# 2_matrix.net
KiCad netlist of a schematic drawn in Altium Designer
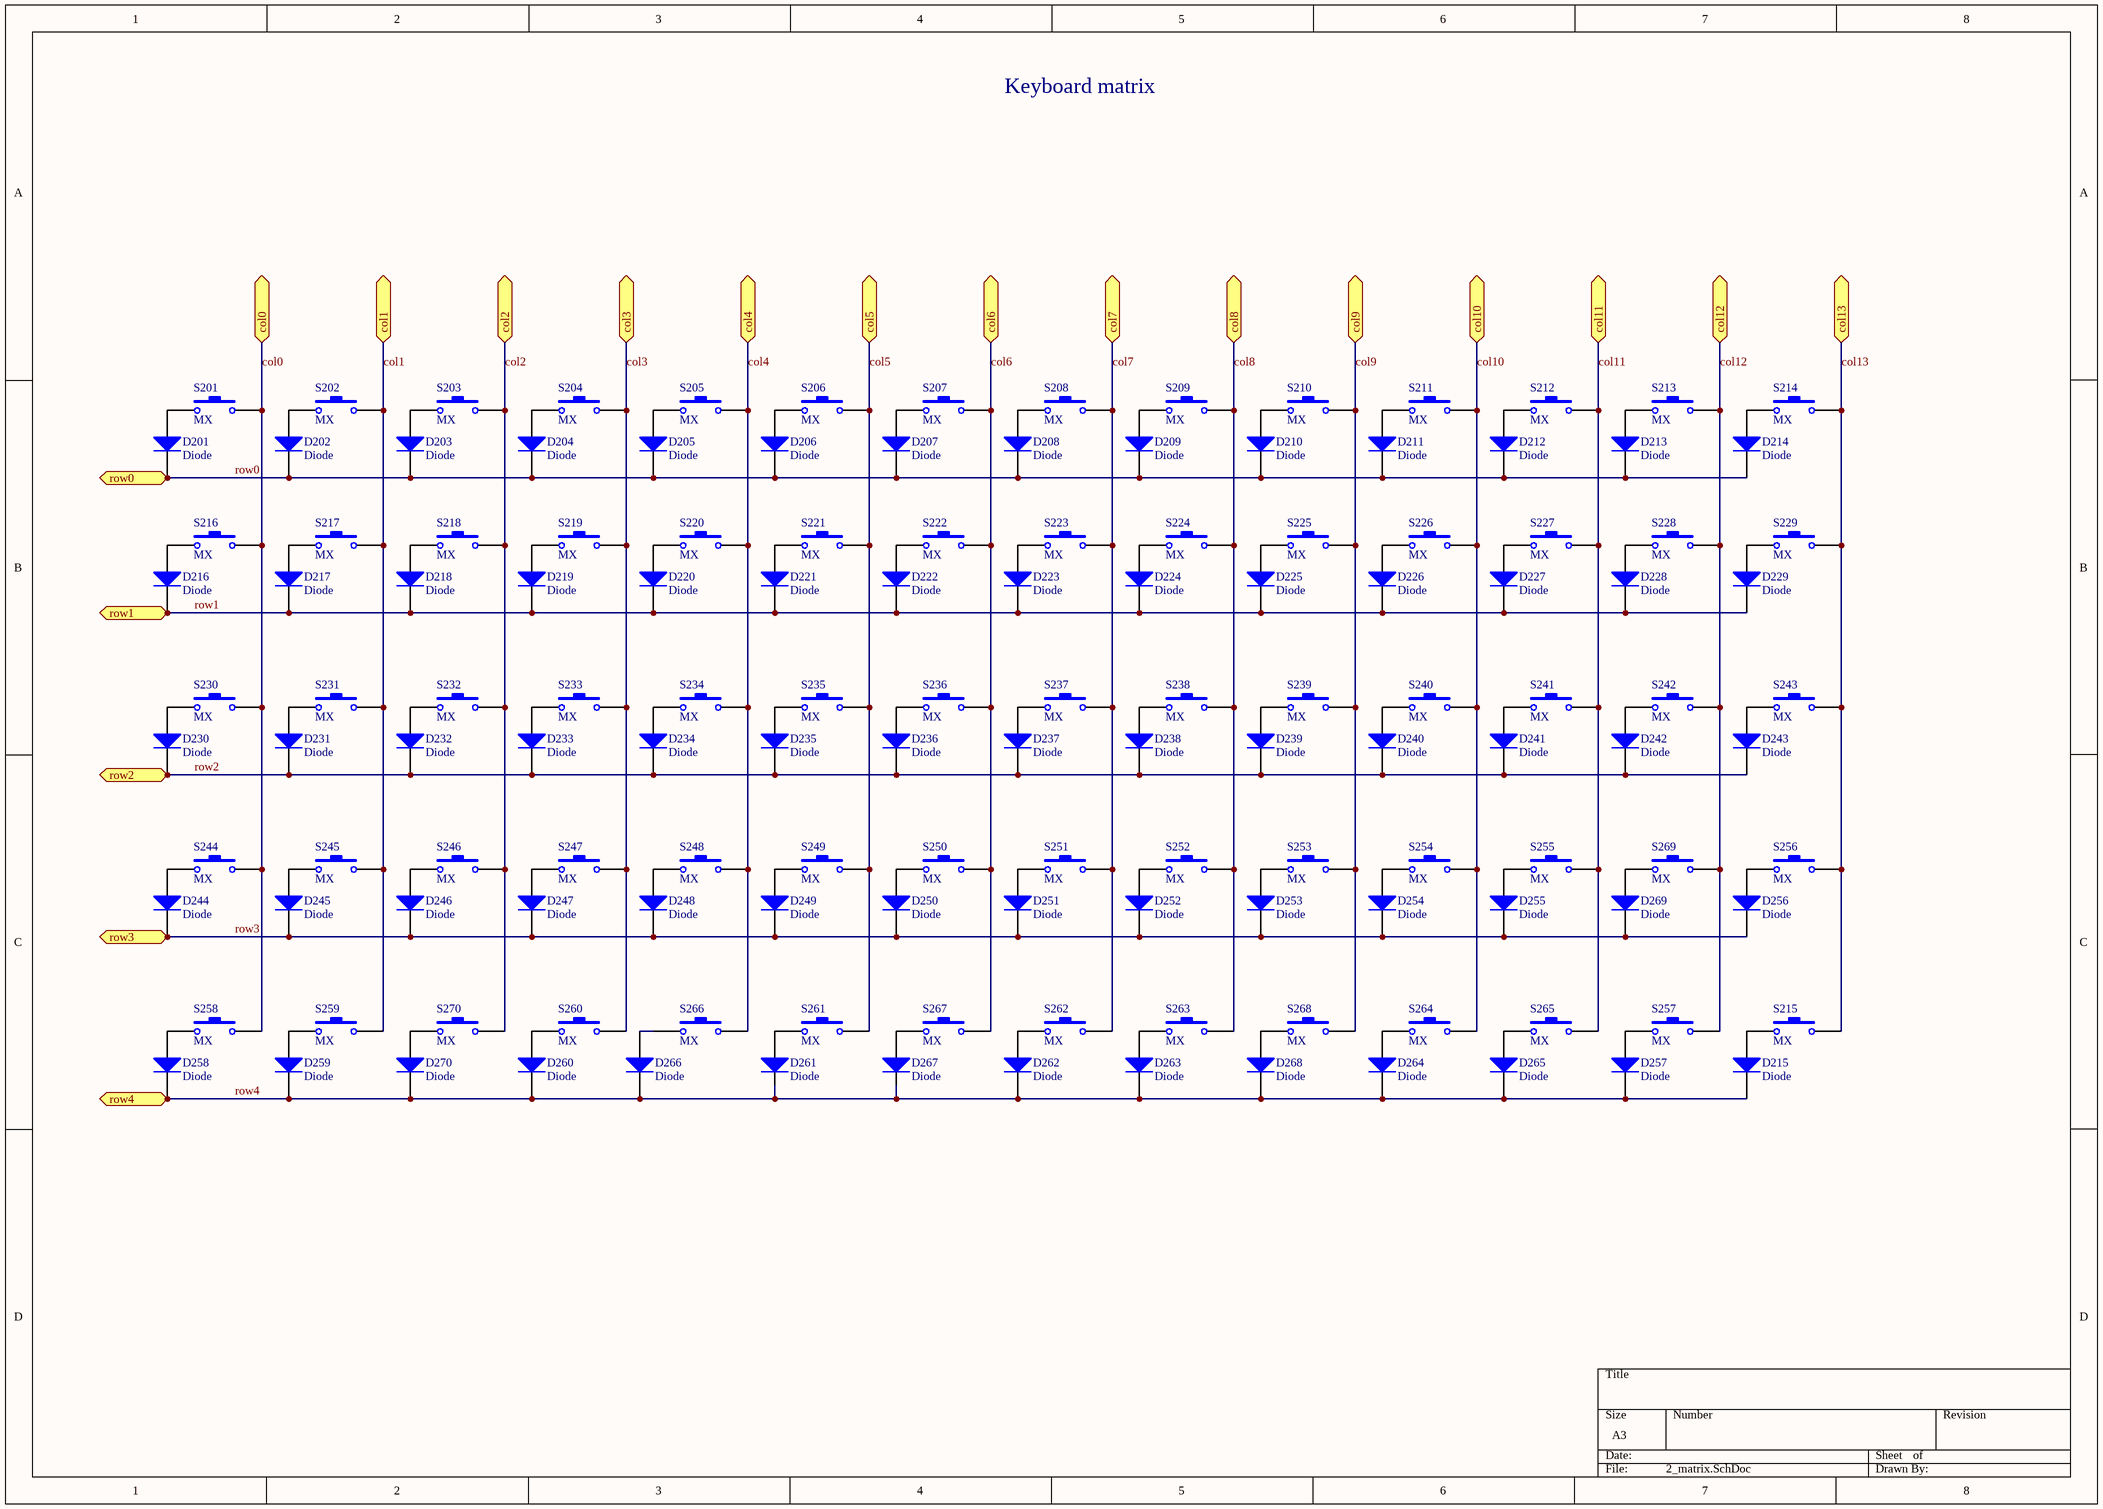
[diagram p0: 2_matrix.SchDoc]

(export (version "E")
  (design (tool "Eeschema 10.0.6"))
  (components
    (comp (ref "D201")
      (value "Diode")
      (footprint "D0603[1608]")
      (description "Default Diode")
      (fields (field (name "MFG") "Bourns Inc.") (field (name "MRF.PART") "CD4148WTP"))
      (libsource (lib "Miscellaneous Devices") (part "Diode"))
    )
    (comp (ref "D202")
      (value "Diode")
      (footprint "D0603[1608]")
      (description "Default Diode")
      (fields (field (name "MFG") "Bourns Inc.") (field (name "MRF.PART") "CD4148WTP"))
      (libsource (lib "Miscellaneous Devices") (part "Diode"))
    )
    (comp (ref "D203")
      (value "Diode")
      (footprint "D0603[1608]")
      (description "Default Diode")
      (fields (field (name "MFG") "Bourns Inc.") (field (name "MRF.PART") "CD4148WTP"))
      (libsource (lib "Miscellaneous Devices") (part "Diode"))
    )
    (comp (ref "D204")
      (value "Diode")
      (footprint "D0603[1608]")
      (description "Default Diode")
      (fields (field (name "MFG") "Bourns Inc.") (field (name "MRF.PART") "CD4148WTP"))
      (libsource (lib "Miscellaneous Devices") (part "Diode"))
    )
    (comp (ref "D205")
      (value "Diode")
      (footprint "D0603[1608]")
      (description "Default Diode")
      (fields (field (name "MFG") "Bourns Inc.") (field (name "MRF.PART") "CD4148WTP"))
      (libsource (lib "Miscellaneous Devices") (part "Diode"))
    )
    (comp (ref "D206")
      (value "Diode")
      (footprint "D0603[1608]")
      (description "Default Diode")
      (fields (field (name "MFG") "Bourns Inc.") (field (name "MRF.PART") "CD4148WTP"))
      (libsource (lib "Miscellaneous Devices") (part "Diode"))
    )
    (comp (ref "D207")
      (value "Diode")
      (footprint "D0603[1608]")
      (description "Default Diode")
      (fields (field (name "MFG") "Bourns Inc.") (field (name "MRF.PART") "CD4148WTP"))
      (libsource (lib "Miscellaneous Devices") (part "Diode"))
    )
    (comp (ref "D208")
      (value "Diode")
      (footprint "D0603[1608]")
      (description "Default Diode")
      (fields (field (name "MFG") "Bourns Inc.") (field (name "MRF.PART") "CD4148WTP"))
      (libsource (lib "Miscellaneous Devices") (part "Diode"))
    )
    (comp (ref "D209")
      (value "Diode")
      (footprint "D0603[1608]")
      (description "Default Diode")
      (fields (field (name "MFG") "Bourns Inc.") (field (name "MRF.PART") "CD4148WTP"))
      (libsource (lib "Miscellaneous Devices") (part "Diode"))
    )
    (comp (ref "D210")
      (value "Diode")
      (footprint "D0603[1608]")
      (description "Default Diode")
      (fields (field (name "MFG") "Bourns Inc.") (field (name "MRF.PART") "CD4148WTP"))
      (libsource (lib "Miscellaneous Devices") (part "Diode"))
    )
    (comp (ref "D211")
      (value "Diode")
      (footprint "D0603[1608]")
      (description "Default Diode")
      (fields (field (name "MFG") "Bourns Inc.") (field (name "MRF.PART") "CD4148WTP"))
      (libsource (lib "Miscellaneous Devices") (part "Diode"))
    )
    (comp (ref "D212")
      (value "Diode")
      (footprint "D0603[1608]")
      (description "Default Diode")
      (fields (field (name "MFG") "Bourns Inc.") (field (name "MRF.PART") "CD4148WTP"))
      (libsource (lib "Miscellaneous Devices") (part "Diode"))
    )
    (comp (ref "D213")
      (value "Diode")
      (footprint "D0603[1608]")
      (description "Default Diode")
      (fields (field (name "MFG") "Bourns Inc.") (field (name "MRF.PART") "CD4148WTP"))
      (libsource (lib "Miscellaneous Devices") (part "Diode"))
    )
    (comp (ref "D214")
      (value "Diode")
      (footprint "D0603[1608]")
      (description "Default Diode")
      (fields (field (name "MFG") "Bourns Inc.") (field (name "MRF.PART") "CD4148WTP"))
      (libsource (lib "Miscellaneous Devices") (part "Diode"))
    )
    (comp (ref "D215")
      (value "Diode")
      (footprint "D0603[1608]")
      (description "Default Diode")
      (fields (field (name "MFG") "Bourns Inc.") (field (name "MRF.PART") "CD4148WTP"))
      (libsource (lib "Miscellaneous Devices") (part "Diode"))
    )
    (comp (ref "D216")
      (value "Diode")
      (footprint "D0603[1608]")
      (description "Default Diode")
      (fields (field (name "MFG") "Bourns Inc.") (field (name "MRF.PART") "CD4148WTP"))
      (libsource (lib "Miscellaneous Devices") (part "Diode"))
    )
    (comp (ref "D217")
      (value "Diode")
      (footprint "D0603[1608]")
      (description "Default Diode")
      (fields (field (name "MFG") "Bourns Inc.") (field (name "MRF.PART") "CD4148WTP"))
      (libsource (lib "Miscellaneous Devices") (part "Diode"))
    )
    (comp (ref "D218")
      (value "Diode")
      (footprint "D0603[1608]")
      (description "Default Diode")
      (fields (field (name "MFG") "Bourns Inc.") (field (name "MRF.PART") "CD4148WTP"))
      (libsource (lib "Miscellaneous Devices") (part "Diode"))
    )
    (comp (ref "D219")
      (value "Diode")
      (footprint "D0603[1608]")
      (description "Default Diode")
      (fields (field (name "MFG") "Bourns Inc.") (field (name "MRF.PART") "CD4148WTP"))
      (libsource (lib "Miscellaneous Devices") (part "Diode"))
    )
    (comp (ref "D220")
      (value "Diode")
      (footprint "D0603[1608]")
      (description "Default Diode")
      (fields (field (name "MFG") "Bourns Inc.") (field (name "MRF.PART") "CD4148WTP"))
      (libsource (lib "Miscellaneous Devices") (part "Diode"))
    )
    (comp (ref "D221")
      (value "Diode")
      (footprint "D0603[1608]")
      (description "Default Diode")
      (fields (field (name "MFG") "Bourns Inc.") (field (name "MRF.PART") "CD4148WTP"))
      (libsource (lib "Miscellaneous Devices") (part "Diode"))
    )
    (comp (ref "D222")
      (value "Diode")
      (footprint "D0603[1608]")
      (description "Default Diode")
      (fields (field (name "MFG") "Bourns Inc.") (field (name "MRF.PART") "CD4148WTP"))
      (libsource (lib "Miscellaneous Devices") (part "Diode"))
    )
    (comp (ref "D223")
      (value "Diode")
      (footprint "D0603[1608]")
      (description "Default Diode")
      (fields (field (name "MFG") "Bourns Inc.") (field (name "MRF.PART") "CD4148WTP"))
      (libsource (lib "Miscellaneous Devices") (part "Diode"))
    )
    (comp (ref "D224")
      (value "Diode")
      (footprint "D0603[1608]")
      (description "Default Diode")
      (fields (field (name "MFG") "Bourns Inc.") (field (name "MRF.PART") "CD4148WTP"))
      (libsource (lib "Miscellaneous Devices") (part "Diode"))
    )
    (comp (ref "D225")
      (value "Diode")
      (footprint "D0603[1608]")
      (description "Default Diode")
      (fields (field (name "MFG") "Bourns Inc.") (field (name "MRF.PART") "CD4148WTP"))
      (libsource (lib "Miscellaneous Devices") (part "Diode"))
    )
    (comp (ref "D226")
      (value "Diode")
      (footprint "D0603[1608]")
      (description "Default Diode")
      (fields (field (name "MFG") "Bourns Inc.") (field (name "MRF.PART") "CD4148WTP"))
      (libsource (lib "Miscellaneous Devices") (part "Diode"))
    )
    (comp (ref "D227")
      (value "Diode")
      (footprint "D0603[1608]")
      (description "Default Diode")
      (fields (field (name "MFG") "Bourns Inc.") (field (name "MRF.PART") "CD4148WTP"))
      (libsource (lib "Miscellaneous Devices") (part "Diode"))
    )
    (comp (ref "D228")
      (value "Diode")
      (footprint "D0603[1608]")
      (description "Default Diode")
      (fields (field (name "MFG") "Bourns Inc.") (field (name "MRF.PART") "CD4148WTP"))
      (libsource (lib "Miscellaneous Devices") (part "Diode"))
    )
    (comp (ref "D229")
      (value "Diode")
      (footprint "D0603[1608]")
      (description "Default Diode")
      (fields (field (name "MFG") "Bourns Inc.") (field (name "MRF.PART") "CD4148WTP"))
      (libsource (lib "Miscellaneous Devices") (part "Diode"))
    )
    (comp (ref "D230")
      (value "Diode")
      (footprint "D0603[1608]")
      (description "Default Diode")
      (fields (field (name "MFG") "Bourns Inc.") (field (name "MRF.PART") "CD4148WTP"))
      (libsource (lib "Miscellaneous Devices") (part "Diode"))
    )
    (comp (ref "D231")
      (value "Diode")
      (footprint "D0603[1608]")
      (description "Default Diode")
      (fields (field (name "MFG") "Bourns Inc.") (field (name "MRF.PART") "CD4148WTP"))
      (libsource (lib "Miscellaneous Devices") (part "Diode"))
    )
    (comp (ref "D232")
      (value "Diode")
      (footprint "D0603[1608]")
      (description "Default Diode")
      (fields (field (name "MFG") "Bourns Inc.") (field (name "MRF.PART") "CD4148WTP"))
      (libsource (lib "Miscellaneous Devices") (part "Diode"))
    )
    (comp (ref "D233")
      (value "Diode")
      (footprint "D0603[1608]")
      (description "Default Diode")
      (fields (field (name "MFG") "Bourns Inc.") (field (name "MRF.PART") "CD4148WTP"))
      (libsource (lib "Miscellaneous Devices") (part "Diode"))
    )
    (comp (ref "D234")
      (value "Diode")
      (footprint "D0603[1608]")
      (description "Default Diode")
      (fields (field (name "MFG") "Bourns Inc.") (field (name "MRF.PART") "CD4148WTP"))
      (libsource (lib "Miscellaneous Devices") (part "Diode"))
    )
    (comp (ref "D235")
      (value "Diode")
      (footprint "D0603[1608]")
      (description "Default Diode")
      (fields (field (name "MFG") "Bourns Inc.") (field (name "MRF.PART") "CD4148WTP"))
      (libsource (lib "Miscellaneous Devices") (part "Diode"))
    )
    (comp (ref "D236")
      (value "Diode")
      (footprint "D0603[1608]")
      (description "Default Diode")
      (fields (field (name "MFG") "Bourns Inc.") (field (name "MRF.PART") "CD4148WTP"))
      (libsource (lib "Miscellaneous Devices") (part "Diode"))
    )
    (comp (ref "D237")
      (value "Diode")
      (footprint "D0603[1608]")
      (description "Default Diode")
      (fields (field (name "MFG") "Bourns Inc.") (field (name "MRF.PART") "CD4148WTP"))
      (libsource (lib "Miscellaneous Devices") (part "Diode"))
    )
    (comp (ref "D238")
      (value "Diode")
      (footprint "D0603[1608]")
      (description "Default Diode")
      (fields (field (name "MFG") "Bourns Inc.") (field (name "MRF.PART") "CD4148WTP"))
      (libsource (lib "Miscellaneous Devices") (part "Diode"))
    )
    (comp (ref "D239")
      (value "Diode")
      (footprint "D0603[1608]")
      (description "Default Diode")
      (fields (field (name "MFG") "Bourns Inc.") (field (name "MRF.PART") "CD4148WTP"))
      (libsource (lib "Miscellaneous Devices") (part "Diode"))
    )
    (comp (ref "D240")
      (value "Diode")
      (footprint "D0603[1608]")
      (description "Default Diode")
      (fields (field (name "MFG") "Bourns Inc.") (field (name "MRF.PART") "CD4148WTP"))
      (libsource (lib "Miscellaneous Devices") (part "Diode"))
    )
    (comp (ref "D241")
      (value "Diode")
      (footprint "D0603[1608]")
      (description "Default Diode")
      (fields (field (name "MFG") "Bourns Inc.") (field (name "MRF.PART") "CD4148WTP"))
      (libsource (lib "Miscellaneous Devices") (part "Diode"))
    )
    (comp (ref "D242")
      (value "Diode")
      (footprint "D0603[1608]")
      (description "Default Diode")
      (fields (field (name "MFG") "Bourns Inc.") (field (name "MRF.PART") "CD4148WTP"))
      (libsource (lib "Miscellaneous Devices") (part "Diode"))
    )
    (comp (ref "D243")
      (value "Diode")
      (footprint "D0603[1608]")
      (description "Default Diode")
      (fields (field (name "MFG") "Bourns Inc.") (field (name "MRF.PART") "CD4148WTP"))
      (libsource (lib "Miscellaneous Devices") (part "Diode"))
    )
    (comp (ref "D244")
      (value "Diode")
      (footprint "D0603[1608]")
      (description "Default Diode")
      (fields (field (name "MFG") "Bourns Inc.") (field (name "MRF.PART") "CD4148WTP"))
      (libsource (lib "Miscellaneous Devices") (part "Diode"))
    )
    (comp (ref "D245")
      (value "Diode")
      (footprint "D0603[1608]")
      (description "Default Diode")
      (fields (field (name "MFG") "Bourns Inc.") (field (name "MRF.PART") "CD4148WTP"))
      (libsource (lib "Miscellaneous Devices") (part "Diode"))
    )
    (comp (ref "D246")
      (value "Diode")
      (footprint "D0603[1608]")
      (description "Default Diode")
      (fields (field (name "MFG") "Bourns Inc.") (field (name "MRF.PART") "CD4148WTP"))
      (libsource (lib "Miscellaneous Devices") (part "Diode"))
    )
    (comp (ref "D247")
      (value "Diode")
      (footprint "D0603[1608]")
      (description "Default Diode")
      (fields (field (name "MFG") "Bourns Inc.") (field (name "MRF.PART") "CD4148WTP"))
      (libsource (lib "Miscellaneous Devices") (part "Diode"))
    )
    (comp (ref "D248")
      (value "Diode")
      (footprint "D0603[1608]")
      (description "Default Diode")
      (fields (field (name "MFG") "Bourns Inc.") (field (name "MRF.PART") "CD4148WTP"))
      (libsource (lib "Miscellaneous Devices") (part "Diode"))
    )
    (comp (ref "D249")
      (value "Diode")
      (footprint "D0603[1608]")
      (description "Default Diode")
      (fields (field (name "MFG") "Bourns Inc.") (field (name "MRF.PART") "CD4148WTP"))
      (libsource (lib "Miscellaneous Devices") (part "Diode"))
    )
    (comp (ref "D250")
      (value "Diode")
      (footprint "D0603[1608]")
      (description "Default Diode")
      (fields (field (name "MFG") "Bourns Inc.") (field (name "MRF.PART") "CD4148WTP"))
      (libsource (lib "Miscellaneous Devices") (part "Diode"))
    )
    (comp (ref "D251")
      (value "Diode")
      (footprint "D0603[1608]")
      (description "Default Diode")
      (fields (field (name "MFG") "Bourns Inc.") (field (name "MRF.PART") "CD4148WTP"))
      (libsource (lib "Miscellaneous Devices") (part "Diode"))
    )
    (comp (ref "D252")
      (value "Diode")
      (footprint "D0603[1608]")
      (description "Default Diode")
      (fields (field (name "MFG") "Bourns Inc.") (field (name "MRF.PART") "CD4148WTP"))
      (libsource (lib "Miscellaneous Devices") (part "Diode"))
    )
    (comp (ref "D253")
      (value "Diode")
      (footprint "D0603[1608]")
      (description "Default Diode")
      (fields (field (name "MFG") "Bourns Inc.") (field (name "MRF.PART") "CD4148WTP"))
      (libsource (lib "Miscellaneous Devices") (part "Diode"))
    )
    (comp (ref "D254")
      (value "Diode")
      (footprint "D0603[1608]")
      (description "Default Diode")
      (fields (field (name "MFG") "Bourns Inc.") (field (name "MRF.PART") "CD4148WTP"))
      (libsource (lib "Miscellaneous Devices") (part "Diode"))
    )
    (comp (ref "D255")
      (value "Diode")
      (footprint "D0603[1608]")
      (description "Default Diode")
      (fields (field (name "MFG") "Bourns Inc.") (field (name "MRF.PART") "CD4148WTP"))
      (libsource (lib "Miscellaneous Devices") (part "Diode"))
    )
    (comp (ref "D256")
      (value "Diode")
      (footprint "D0603[1608]")
      (description "Default Diode")
      (fields (field (name "MFG") "Bourns Inc.") (field (name "MRF.PART") "CD4148WTP"))
      (libsource (lib "Miscellaneous Devices") (part "Diode"))
    )
    (comp (ref "D257")
      (value "Diode")
      (footprint "D0603[1608]")
      (description "Default Diode")
      (fields (field (name "MFG") "Bourns Inc.") (field (name "MRF.PART") "CD4148WTP"))
      (libsource (lib "Miscellaneous Devices") (part "Diode"))
    )
    (comp (ref "D258")
      (value "Diode")
      (footprint "D0603[1608]")
      (description "Default Diode")
      (fields (field (name "MFG") "Bourns Inc.") (field (name "MRF.PART") "CD4148WTP"))
      (libsource (lib "Miscellaneous Devices") (part "Diode"))
    )
    (comp (ref "D259")
      (value "Diode")
      (footprint "D0603[1608]")
      (description "Default Diode")
      (fields (field (name "MFG") "Bourns Inc.") (field (name "MRF.PART") "CD4148WTP"))
      (libsource (lib "Miscellaneous Devices") (part "Diode"))
    )
    (comp (ref "D260")
      (value "Diode")
      (footprint "D0603[1608]")
      (description "Default Diode")
      (fields (field (name "MFG") "Bourns Inc.") (field (name "MRF.PART") "CD4148WTP"))
      (libsource (lib "Miscellaneous Devices") (part "Diode"))
    )
    (comp (ref "D261")
      (value "Diode")
      (footprint "D0603[1608]")
      (description "Default Diode")
      (fields (field (name "MFG") "Bourns Inc.") (field (name "MRF.PART") "CD4148WTP"))
      (libsource (lib "Miscellaneous Devices") (part "Diode"))
    )
    (comp (ref "D262")
      (value "Diode")
      (footprint "D0603[1608]")
      (description "Default Diode")
      (fields (field (name "MFG") "Bourns Inc.") (field (name "MRF.PART") "CD4148WTP"))
      (libsource (lib "Miscellaneous Devices") (part "Diode"))
    )
    (comp (ref "D263")
      (value "Diode")
      (footprint "D0603[1608]")
      (description "Default Diode")
      (fields (field (name "MFG") "Bourns Inc.") (field (name "MRF.PART") "CD4148WTP"))
      (libsource (lib "Miscellaneous Devices") (part "Diode"))
    )
    (comp (ref "D264")
      (value "Diode")
      (footprint "D0603[1608]")
      (description "Default Diode")
      (fields (field (name "MFG") "Bourns Inc.") (field (name "MRF.PART") "CD4148WTP"))
      (libsource (lib "Miscellaneous Devices") (part "Diode"))
    )
    (comp (ref "D265")
      (value "Diode")
      (footprint "D0603[1608]")
      (description "Default Diode")
      (fields (field (name "MFG") "Bourns Inc.") (field (name "MRF.PART") "CD4148WTP"))
      (libsource (lib "Miscellaneous Devices") (part "Diode"))
    )
    (comp (ref "D266")
      (value "Diode")
      (footprint "D0603[1608]")
      (description "Default Diode")
      (fields (field (name "MFG") "Bourns Inc.") (field (name "MRF.PART") "CD4148WTP"))
      (libsource (lib "Miscellaneous Devices") (part "Diode"))
    )
    (comp (ref "D267")
      (value "Diode")
      (footprint "D0603[1608]")
      (description "Default Diode")
      (fields (field (name "MFG") "Bourns Inc.") (field (name "MRF.PART") "CD4148WTP"))
      (libsource (lib "Miscellaneous Devices") (part "Diode"))
    )
    (comp (ref "D268")
      (value "Diode")
      (footprint "D0603[1608]")
      (description "Default Diode")
      (fields (field (name "MFG") "Bourns Inc.") (field (name "MRF.PART") "CD4148WTP"))
      (libsource (lib "Miscellaneous Devices") (part "Diode"))
    )
    (comp (ref "D269")
      (value "Diode")
      (footprint "D0603[1608]")
      (description "Default Diode")
      (fields (field (name "MFG") "Bourns Inc.") (field (name "MRF.PART") "CD4148WTP"))
      (libsource (lib "Miscellaneous Devices") (part "Diode"))
    )
    (comp (ref "D270")
      (value "Diode")
      (footprint "D0603[1608]")
      (description "Default Diode")
      (fields (field (name "MFG") "Bourns Inc.") (field (name "MRF.PART") "CD4148WTP"))
      (libsource (lib "Miscellaneous Devices") (part "Diode"))
    )
    (comp (ref "S201")
      (value "MX")
      (footprint "SMK-switch")
      (description "Switch")
      (libsource (lib "Miscellaneous Devices") (part "SW-PB"))
    )
    (comp (ref "S202")
      (value "MX")
      (footprint "SMK-switch")
      (description "Switch")
      (libsource (lib "Miscellaneous Devices") (part "SW-PB"))
    )
    (comp (ref "S203")
      (value "MX")
      (footprint "SMK-switch")
      (description "Switch")
      (libsource (lib "Miscellaneous Devices") (part "SW-PB"))
    )
    (comp (ref "S204")
      (value "MX")
      (footprint "SMK-switch")
      (description "Switch")
      (libsource (lib "Miscellaneous Devices") (part "SW-PB"))
    )
    (comp (ref "S205")
      (value "MX")
      (footprint "SMK-switch")
      (description "Switch")
      (libsource (lib "Miscellaneous Devices") (part "SW-PB"))
    )
    (comp (ref "S206")
      (value "MX")
      (footprint "SMK-switch")
      (description "Switch")
      (libsource (lib "Miscellaneous Devices") (part "SW-PB"))
    )
    (comp (ref "S207")
      (value "MX")
      (footprint "SMK-switch")
      (description "Switch")
      (libsource (lib "Miscellaneous Devices") (part "SW-PB"))
    )
    (comp (ref "S208")
      (value "MX")
      (footprint "SMK-switch")
      (description "Switch")
      (libsource (lib "Miscellaneous Devices") (part "SW-PB"))
    )
    (comp (ref "S209")
      (value "MX")
      (footprint "SMK-switch")
      (description "Switch")
      (libsource (lib "Miscellaneous Devices") (part "SW-PB"))
    )
    (comp (ref "S210")
      (value "MX")
      (footprint "SMK-switch")
      (description "Switch")
      (libsource (lib "Miscellaneous Devices") (part "SW-PB"))
    )
    (comp (ref "S211")
      (value "MX")
      (footprint "SMK-switch")
      (description "Switch")
      (libsource (lib "Miscellaneous Devices") (part "SW-PB"))
    )
    (comp (ref "S212")
      (value "MX")
      (footprint "SMK-switch")
      (description "Switch")
      (libsource (lib "Miscellaneous Devices") (part "SW-PB"))
    )
    (comp (ref "S213")
      (value "MX")
      (footprint "SMK-switch")
      (description "Switch")
      (libsource (lib "Miscellaneous Devices") (part "SW-PB"))
    )
    (comp (ref "S214")
      (value "MX")
      (footprint "SMK-switch")
      (description "Switch")
      (libsource (lib "Miscellaneous Devices") (part "SW-PB"))
    )
    (comp (ref "S215")
      (value "MX")
      (footprint "SMK-switch - backspace")
      (description "Switch")
      (libsource (lib "Miscellaneous Devices") (part "SW-PB"))
    )
    (comp (ref "S216")
      (value "MX")
      (footprint "SMK-switch - 1.5U")
      (description "TAB")
      (libsource (lib "Miscellaneous Devices") (part "SW-PB"))
    )
    (comp (ref "S217")
      (value "MX")
      (footprint "SMK-switch")
      (description "Switch")
      (libsource (lib "Miscellaneous Devices") (part "SW-PB"))
    )
    (comp (ref "S218")
      (value "MX")
      (footprint "SMK-switch")
      (description "Switch")
      (libsource (lib "Miscellaneous Devices") (part "SW-PB"))
    )
    (comp (ref "S219")
      (value "MX")
      (footprint "SMK-switch")
      (description "Switch")
      (libsource (lib "Miscellaneous Devices") (part "SW-PB"))
    )
    (comp (ref "S220")
      (value "MX")
      (footprint "SMK-switch")
      (description "Switch")
      (libsource (lib "Miscellaneous Devices") (part "SW-PB"))
    )
    (comp (ref "S221")
      (value "MX")
      (footprint "SMK-switch")
      (description "Switch")
      (libsource (lib "Miscellaneous Devices") (part "SW-PB"))
    )
    (comp (ref "S222")
      (value "MX")
      (footprint "SMK-switch")
      (description "Switch")
      (libsource (lib "Miscellaneous Devices") (part "SW-PB"))
    )
    (comp (ref "S223")
      (value "MX")
      (footprint "SMK-switch")
      (description "Switch")
      (libsource (lib "Miscellaneous Devices") (part "SW-PB"))
    )
    (comp (ref "S224")
      (value "MX")
      (footprint "SMK-switch")
      (description "Switch")
      (libsource (lib "Miscellaneous Devices") (part "SW-PB"))
    )
    (comp (ref "S225")
      (value "MX")
      (footprint "SMK-switch")
      (description "Switch")
      (libsource (lib "Miscellaneous Devices") (part "SW-PB"))
    )
    (comp (ref "S226")
      (value "MX")
      (footprint "SMK-switch")
      (description "Switch")
      (libsource (lib "Miscellaneous Devices") (part "SW-PB"))
    )
    (comp (ref "S227")
      (value "MX")
      (footprint "SMK-switch")
      (description "Switch")
      (libsource (lib "Miscellaneous Devices") (part "SW-PB"))
    )
    (comp (ref "S228")
      (value "MX")
      (footprint "SMK-switch - offset-R")
      (description "Switch")
      (libsource (lib "Miscellaneous Devices") (part "SW-PB"))
    )
    (comp (ref "S229")
      (value "MX")
      (footprint "SMK-switch - 1.5U")
      (description "Switch")
      (libsource (lib "Miscellaneous Devices") (part "SW-PB"))
    )
    (comp (ref "S230")
      (value "MX")
      (footprint "SMK-switch - CAPS")
      (description "Switch")
      (libsource (lib "Miscellaneous Devices") (part "SW-PB"))
    )
    (comp (ref "S231")
      (value "MX")
      (footprint "SMK-switch")
      (description "Switch")
      (libsource (lib "Miscellaneous Devices") (part "SW-PB"))
    )
    (comp (ref "S232")
      (value "MX")
      (footprint "SMK-switch")
      (description "Switch")
      (libsource (lib "Miscellaneous Devices") (part "SW-PB"))
    )
    (comp (ref "S233")
      (value "MX")
      (footprint "SMK-switch")
      (description "Switch")
      (libsource (lib "Miscellaneous Devices") (part "SW-PB"))
    )
    (comp (ref "S234")
      (value "MX")
      (footprint "SMK-switch")
      (description "Switch")
      (libsource (lib "Miscellaneous Devices") (part "SW-PB"))
    )
    (comp (ref "S235")
      (value "MX")
      (footprint "SMK-switch")
      (description "Switch")
      (libsource (lib "Miscellaneous Devices") (part "SW-PB"))
    )
    (comp (ref "S236")
      (value "MX")
      (footprint "SMK-switch")
      (description "Switch")
      (libsource (lib "Miscellaneous Devices") (part "SW-PB"))
    )
    (comp (ref "S237")
      (value "MX")
      (footprint "SMK-switch")
      (description "Switch")
      (libsource (lib "Miscellaneous Devices") (part "SW-PB"))
    )
    (comp (ref "S238")
      (value "MX")
      (footprint "SMK-switch")
      (description "Switch")
      (libsource (lib "Miscellaneous Devices") (part "SW-PB"))
    )
    (comp (ref "S239")
      (value "MX")
      (footprint "SMK-switch")
      (description "Switch")
      (libsource (lib "Miscellaneous Devices") (part "SW-PB"))
    )
    (comp (ref "S240")
      (value "MX")
      (footprint "SMK-switch")
      (description "Switch")
      (libsource (lib "Miscellaneous Devices") (part "SW-PB"))
    )
    (comp (ref "S241")
      (value "MX")
      (footprint "SMK-switch")
      (description "Switch")
      (libsource (lib "Miscellaneous Devices") (part "SW-PB"))
    )
    (comp (ref "S242")
      (value "MX")
      (footprint "SMK-switch")
      (description "Switch")
      (libsource (lib "Miscellaneous Devices") (part "SW-PB"))
    )
    (comp (ref "S243")
      (value "MX")
      (footprint "SMK-switch - Enter")
      (description "Switch")
      (libsource (lib "Miscellaneous Devices") (part "SW-PB"))
    )
    (comp (ref "S244")
      (value "MX")
      (footprint "SMK-switch - Left shift")
      (description "Switch")
      (libsource (lib "Miscellaneous Devices") (part "SW-PB"))
    )
    (comp (ref "S245")
      (value "MX")
      (footprint "SMK-switch - smalleroffset-R")
      (description "Switch")
      (libsource (lib "Miscellaneous Devices") (part "SW-PB"))
    )
    (comp (ref "S246")
      (value "MX")
      (footprint "SMK-switch - offset")
      (description "Switch")
      (libsource (lib "Miscellaneous Devices") (part "SW-PB"))
    )
    (comp (ref "S247")
      (value "MX")
      (footprint "SMK-switch - offset")
      (description "Switch")
      (libsource (lib "Miscellaneous Devices") (part "SW-PB"))
    )
    (comp (ref "S248")
      (value "MX")
      (footprint "SMK-switch - offset")
      (description "Switch")
      (libsource (lib "Miscellaneous Devices") (part "SW-PB"))
    )
    (comp (ref "S249")
      (value "MX")
      (footprint "SMK-switch - offset")
      (description "Switch")
      (libsource (lib "Miscellaneous Devices") (part "SW-PB"))
    )
    (comp (ref "S250")
      (value "MX")
      (footprint "SMK-switch - offset")
      (description "Switch")
      (libsource (lib "Miscellaneous Devices") (part "SW-PB"))
    )
    (comp (ref "S251")
      (value "MX")
      (footprint "SMK-switch - offset")
      (description "Switch")
      (libsource (lib "Miscellaneous Devices") (part "SW-PB"))
    )
    (comp (ref "S252")
      (value "MX")
      (footprint "SMK-switch - offset")
      (description "Switch")
      (libsource (lib "Miscellaneous Devices") (part "SW-PB"))
    )
    (comp (ref "S253")
      (value "MX")
      (footprint "SMK-switch - offset")
      (description "Switch")
      (libsource (lib "Miscellaneous Devices") (part "SW-PB"))
    )
    (comp (ref "S254")
      (value "MX")
      (footprint "SMK-switch - offset")
      (description "Switch")
      (libsource (lib "Miscellaneous Devices") (part "SW-PB"))
    )
    (comp (ref "S255")
      (value "MX")
      (footprint "SMK-switch - offset")
      (description "Switch")
      (libsource (lib "Miscellaneous Devices") (part "SW-PB"))
    )
    (comp (ref "S256")
      (value "MX")
      (footprint "SMK-switch - right shift")
      (description "Switch")
      (libsource (lib "Miscellaneous Devices") (part "SW-PB"))
    )
    (comp (ref "S257")
      (value "MX")
      (footprint "SMK-switch - fn and shift")
      (description "Switch")
      (libsource (lib "Miscellaneous Devices") (part "SW-PB"))
    )
    (comp (ref "S258")
      (value "MX")
      (footprint "SMK-switch - L_CTRL")
      (description "Switch")
      (libsource (lib "Miscellaneous Devices") (part "SW-PB"))
    )
    (comp (ref "S259")
      (value "MX")
      (footprint "SMK-switch - L_WIN")
      (description "Switch")
      (libsource (lib "Miscellaneous Devices") (part "SW-PB"))
    )
    (comp (ref "S260")
      (value "MX")
      (footprint "SMK-switch - L_alt")
      (description "Switch")
      (libsource (lib "Miscellaneous Devices") (part "SW-PB"))
    )
    (comp (ref "S261")
      (value "MX")
      (footprint "SMK-switch - Space")
      (description "Switch")
      (libsource (lib "Miscellaneous Devices") (part "SW-PB"))
    )
    (comp (ref "S262")
      (value "MX")
      (footprint "SMK-switch - R PN")
      (description "Switch")
      (libsource (lib "Miscellaneous Devices") (part "SW-PB"))
    )
    (comp (ref "S263")
      (value "MX")
      (footprint "SMK-switch - R_alt")
      (description "Switch")
      (libsource (lib "Miscellaneous Devices") (part "SW-PB"))
    )
    (comp (ref "S264")
      (value "MX")
      (footprint "SMK-switch - R_WIN")
      (description "Switch")
      (libsource (lib "Miscellaneous Devices") (part "SW-PB"))
    )
    (comp (ref "S265")
      (value "MX")
      (footprint "SMK-switch - R_CTRL")
      (description "Switch")
      (libsource (lib "Miscellaneous Devices") (part "SW-PB"))
    )
    (comp (ref "S266")
      (value "MX")
      (footprint "SMK-switch - L split space")
      (description "Switch")
      (libsource (lib "Miscellaneous Devices") (part "SW-PB"))
    )
    (comp (ref "S267")
      (value "MX")
      (footprint "SMK-switch - R split space")
      (description "Switch")
      (libsource (lib "Miscellaneous Devices") (part "SW-PB"))
    )
    (comp (ref "S268")
      (value "MX")
      (footprint "SMK-switch")
      (description "Switch")
      (libsource (lib "Miscellaneous Devices") (part "SW-PB"))
    )
    (comp (ref "S269")
      (value "MX")
      (footprint "SMK-switch - CRAZY SHIFT")
      (description "Switch")
      (libsource (lib "Miscellaneous Devices") (part "SW-PB"))
    )
    (comp (ref "S270")
      (value "MX")
      (footprint "SMK-switch")
      (description "Switch")
      (libsource (lib "Miscellaneous Devices") (part "SW-PB"))
    )
  )
  (nets
    (net (code "1") (name "/col0") (class "Default")
      (node (ref "S201") (pin "2") (pinfunction "2_2") (pintype "passive"))
      (node (ref "S216") (pin "2") (pinfunction "2_2") (pintype "passive"))
      (node (ref "S230") (pin "2") (pinfunction "2_2") (pintype "passive"))
      (node (ref "S244") (pin "2") (pinfunction "2_2") (pintype "passive"))
      (node (ref "S258") (pin "2") (pinfunction "2_2") (pintype "passive"))
    )
    (net (code "2") (name "/col1") (class "Default")
      (node (ref "S202") (pin "2") (pinfunction "2_2") (pintype "passive"))
      (node (ref "S217") (pin "2") (pinfunction "2_2") (pintype "passive"))
      (node (ref "S231") (pin "2") (pinfunction "2_2") (pintype "passive"))
      (node (ref "S245") (pin "2") (pinfunction "2_2") (pintype "passive"))
      (node (ref "S259") (pin "2") (pinfunction "2_2") (pintype "passive"))
    )
    (net (code "3") (name "/col2") (class "Default")
      (node (ref "S203") (pin "2") (pinfunction "2_2") (pintype "passive"))
      (node (ref "S218") (pin "2") (pinfunction "2_2") (pintype "passive"))
      (node (ref "S232") (pin "2") (pinfunction "2_2") (pintype "passive"))
      (node (ref "S246") (pin "2") (pinfunction "2_2") (pintype "passive"))
      (node (ref "S270") (pin "2") (pinfunction "2_2") (pintype "passive"))
    )
    (net (code "4") (name "/col3") (class "Default")
      (node (ref "S204") (pin "2") (pinfunction "2_2") (pintype "passive"))
      (node (ref "S219") (pin "2") (pinfunction "2_2") (pintype "passive"))
      (node (ref "S233") (pin "2") (pinfunction "2_2") (pintype "passive"))
      (node (ref "S247") (pin "2") (pinfunction "2_2") (pintype "passive"))
      (node (ref "S260") (pin "2") (pinfunction "2_2") (pintype "passive"))
    )
    (net (code "5") (name "/col4") (class "Default")
      (node (ref "S205") (pin "2") (pinfunction "2_2") (pintype "passive"))
      (node (ref "S220") (pin "2") (pinfunction "2_2") (pintype "passive"))
      (node (ref "S234") (pin "2") (pinfunction "2_2") (pintype "passive"))
      (node (ref "S248") (pin "2") (pinfunction "2_2") (pintype "passive"))
      (node (ref "S266") (pin "2") (pinfunction "2_2") (pintype "passive"))
    )
    (net (code "6") (name "/col5") (class "Default")
      (node (ref "S206") (pin "2") (pinfunction "2_2") (pintype "passive"))
      (node (ref "S221") (pin "2") (pinfunction "2_2") (pintype "passive"))
      (node (ref "S235") (pin "2") (pinfunction "2_2") (pintype "passive"))
      (node (ref "S249") (pin "2") (pinfunction "2_2") (pintype "passive"))
      (node (ref "S261") (pin "2") (pinfunction "2_2") (pintype "passive"))
    )
    (net (code "7") (name "/col6") (class "Default")
      (node (ref "S207") (pin "2") (pinfunction "2_2") (pintype "passive"))
      (node (ref "S222") (pin "2") (pinfunction "2_2") (pintype "passive"))
      (node (ref "S236") (pin "2") (pinfunction "2_2") (pintype "passive"))
      (node (ref "S250") (pin "2") (pinfunction "2_2") (pintype "passive"))
      (node (ref "S267") (pin "2") (pinfunction "2_2") (pintype "passive"))
    )
    (net (code "8") (name "/col7") (class "Default")
      (node (ref "S208") (pin "2") (pinfunction "2_2") (pintype "passive"))
      (node (ref "S223") (pin "2") (pinfunction "2_2") (pintype "passive"))
      (node (ref "S237") (pin "2") (pinfunction "2_2") (pintype "passive"))
      (node (ref "S251") (pin "2") (pinfunction "2_2") (pintype "passive"))
      (node (ref "S262") (pin "2") (pinfunction "2_2") (pintype "passive"))
    )
    (net (code "9") (name "/col8") (class "Default")
      (node (ref "S209") (pin "2") (pinfunction "2_2") (pintype "passive"))
      (node (ref "S224") (pin "2") (pinfunction "2_2") (pintype "passive"))
      (node (ref "S238") (pin "2") (pinfunction "2_2") (pintype "passive"))
      (node (ref "S252") (pin "2") (pinfunction "2_2") (pintype "passive"))
      (node (ref "S263") (pin "2") (pinfunction "2_2") (pintype "passive"))
    )
    (net (code "10") (name "/col9") (class "Default")
      (node (ref "S210") (pin "2") (pinfunction "2_2") (pintype "passive"))
      (node (ref "S225") (pin "2") (pinfunction "2_2") (pintype "passive"))
      (node (ref "S239") (pin "2") (pinfunction "2_2") (pintype "passive"))
      (node (ref "S253") (pin "2") (pinfunction "2_2") (pintype "passive"))
      (node (ref "S268") (pin "2") (pinfunction "2_2") (pintype "passive"))
    )
    (net (code "11") (name "/col10") (class "Default")
      (node (ref "S211") (pin "2") (pinfunction "2_2") (pintype "passive"))
      (node (ref "S226") (pin "2") (pinfunction "2_2") (pintype "passive"))
      (node (ref "S240") (pin "2") (pinfunction "2_2") (pintype "passive"))
      (node (ref "S254") (pin "2") (pinfunction "2_2") (pintype "passive"))
      (node (ref "S264") (pin "2") (pinfunction "2_2") (pintype "passive"))
    )
    (net (code "12") (name "/col11") (class "Default")
      (node (ref "S212") (pin "2") (pinfunction "2_2") (pintype "passive"))
      (node (ref "S227") (pin "2") (pinfunction "2_2") (pintype "passive"))
      (node (ref "S241") (pin "2") (pinfunction "2_2") (pintype "passive"))
      (node (ref "S255") (pin "2") (pinfunction "2_2") (pintype "passive"))
      (node (ref "S265") (pin "2") (pinfunction "2_2") (pintype "passive"))
    )
    (net (code "13") (name "/col12") (class "Default")
      (node (ref "S213") (pin "2") (pinfunction "2_2") (pintype "passive"))
      (node (ref "S228") (pin "2") (pinfunction "2_2") (pintype "passive"))
      (node (ref "S242") (pin "2") (pinfunction "2_2") (pintype "passive"))
      (node (ref "S257") (pin "2") (pinfunction "2_2") (pintype "passive"))
      (node (ref "S269") (pin "2") (pinfunction "2_2") (pintype "passive"))
    )
    (net (code "14") (name "/col13") (class "Default")
      (node (ref "S214") (pin "2") (pinfunction "2_2") (pintype "passive"))
      (node (ref "S215") (pin "2") (pinfunction "2_2") (pintype "passive"))
      (node (ref "S229") (pin "2") (pinfunction "2_2") (pintype "passive"))
      (node (ref "S243") (pin "2") (pinfunction "2_2") (pintype "passive"))
      (node (ref "S256") (pin "2") (pinfunction "2_2") (pintype "passive"))
    )
    (net (code "15") (name "/row0") (class "Default")
      (node (ref "D201") (pin "2") (pinfunction "K_2") (pintype "passive"))
      (node (ref "D202") (pin "2") (pinfunction "K_2") (pintype "passive"))
      (node (ref "D203") (pin "2") (pinfunction "K_2") (pintype "passive"))
      (node (ref "D204") (pin "2") (pinfunction "K_2") (pintype "passive"))
      (node (ref "D205") (pin "2") (pinfunction "K_2") (pintype "passive"))
      (node (ref "D206") (pin "2") (pinfunction "K_2") (pintype "passive"))
      (node (ref "D207") (pin "2") (pinfunction "K_2") (pintype "passive"))
      (node (ref "D208") (pin "2") (pinfunction "K_2") (pintype "passive"))
      (node (ref "D209") (pin "2") (pinfunction "K_2") (pintype "passive"))
      (node (ref "D210") (pin "2") (pinfunction "K_2") (pintype "passive"))
      (node (ref "D211") (pin "2") (pinfunction "K_2") (pintype "passive"))
      (node (ref "D212") (pin "2") (pinfunction "K_2") (pintype "passive"))
      (node (ref "D213") (pin "2") (pinfunction "K_2") (pintype "passive"))
      (node (ref "D214") (pin "2") (pinfunction "K_2") (pintype "passive"))
    )
    (net (code "16") (name "/row1") (class "Default")
      (node (ref "D216") (pin "2") (pinfunction "K_2") (pintype "passive"))
      (node (ref "D217") (pin "2") (pinfunction "K_2") (pintype "passive"))
      (node (ref "D218") (pin "2") (pinfunction "K_2") (pintype "passive"))
      (node (ref "D219") (pin "2") (pinfunction "K_2") (pintype "passive"))
      (node (ref "D220") (pin "2") (pinfunction "K_2") (pintype "passive"))
      (node (ref "D221") (pin "2") (pinfunction "K_2") (pintype "passive"))
      (node (ref "D222") (pin "2") (pinfunction "K_2") (pintype "passive"))
      (node (ref "D223") (pin "2") (pinfunction "K_2") (pintype "passive"))
      (node (ref "D224") (pin "2") (pinfunction "K_2") (pintype "passive"))
      (node (ref "D225") (pin "2") (pinfunction "K_2") (pintype "passive"))
      (node (ref "D226") (pin "2") (pinfunction "K_2") (pintype "passive"))
      (node (ref "D227") (pin "2") (pinfunction "K_2") (pintype "passive"))
      (node (ref "D228") (pin "2") (pinfunction "K_2") (pintype "passive"))
      (node (ref "D229") (pin "2") (pinfunction "K_2") (pintype "passive"))
    )
    (net (code "17") (name "/row2") (class "Default")
      (node (ref "D230") (pin "2") (pinfunction "K_2") (pintype "passive"))
      (node (ref "D231") (pin "2") (pinfunction "K_2") (pintype "passive"))
      (node (ref "D232") (pin "2") (pinfunction "K_2") (pintype "passive"))
      (node (ref "D233") (pin "2") (pinfunction "K_2") (pintype "passive"))
      (node (ref "D234") (pin "2") (pinfunction "K_2") (pintype "passive"))
      (node (ref "D235") (pin "2") (pinfunction "K_2") (pintype "passive"))
      (node (ref "D236") (pin "2") (pinfunction "K_2") (pintype "passive"))
      (node (ref "D237") (pin "2") (pinfunction "K_2") (pintype "passive"))
      (node (ref "D238") (pin "2") (pinfunction "K_2") (pintype "passive"))
      (node (ref "D239") (pin "2") (pinfunction "K_2") (pintype "passive"))
      (node (ref "D240") (pin "2") (pinfunction "K_2") (pintype "passive"))
      (node (ref "D241") (pin "2") (pinfunction "K_2") (pintype "passive"))
      (node (ref "D242") (pin "2") (pinfunction "K_2") (pintype "passive"))
      (node (ref "D243") (pin "2") (pinfunction "K_2") (pintype "passive"))
    )
    (net (code "18") (name "/row3") (class "Default")
      (node (ref "D244") (pin "2") (pinfunction "K_2") (pintype "passive"))
      (node (ref "D245") (pin "2") (pinfunction "K_2") (pintype "passive"))
      (node (ref "D246") (pin "2") (pinfunction "K_2") (pintype "passive"))
      (node (ref "D247") (pin "2") (pinfunction "K_2") (pintype "passive"))
      (node (ref "D248") (pin "2") (pinfunction "K_2") (pintype "passive"))
      (node (ref "D249") (pin "2") (pinfunction "K_2") (pintype "passive"))
      (node (ref "D250") (pin "2") (pinfunction "K_2") (pintype "passive"))
      (node (ref "D251") (pin "2") (pinfunction "K_2") (pintype "passive"))
      (node (ref "D252") (pin "2") (pinfunction "K_2") (pintype "passive"))
      (node (ref "D253") (pin "2") (pinfunction "K_2") (pintype "passive"))
      (node (ref "D254") (pin "2") (pinfunction "K_2") (pintype "passive"))
      (node (ref "D255") (pin "2") (pinfunction "K_2") (pintype "passive"))
      (node (ref "D256") (pin "2") (pinfunction "K_2") (pintype "passive"))
      (node (ref "D269") (pin "2") (pinfunction "K_2") (pintype "passive"))
    )
    (net (code "19") (name "/row4") (class "Default")
      (node (ref "D215") (pin "2") (pinfunction "K_2") (pintype "passive"))
      (node (ref "D257") (pin "2") (pinfunction "K_2") (pintype "passive"))
      (node (ref "D258") (pin "2") (pinfunction "K_2") (pintype "passive"))
      (node (ref "D259") (pin "2") (pinfunction "K_2") (pintype "passive"))
      (node (ref "D260") (pin "2") (pinfunction "K_2") (pintype "passive"))
      (node (ref "D261") (pin "2") (pinfunction "K_2") (pintype "passive"))
      (node (ref "D262") (pin "2") (pinfunction "K_2") (pintype "passive"))
      (node (ref "D263") (pin "2") (pinfunction "K_2") (pintype "passive"))
      (node (ref "D264") (pin "2") (pinfunction "K_2") (pintype "passive"))
      (node (ref "D265") (pin "2") (pinfunction "K_2") (pintype "passive"))
      (node (ref "D266") (pin "2") (pinfunction "K_2") (pintype "passive"))
      (node (ref "D267") (pin "2") (pinfunction "K_2") (pintype "passive"))
      (node (ref "D268") (pin "2") (pinfunction "K_2") (pintype "passive"))
      (node (ref "D270") (pin "2") (pinfunction "K_2") (pintype "passive"))
    )
    (net (code "20") (name "Net-(D201-A)") (class "Default")
      (node (ref "D201") (pin "1") (pinfunction "A_1") (pintype "passive"))
      (node (ref "S201") (pin "1") (pinfunction "1_1") (pintype "passive"))
    )
    (net (code "21") (name "Net-(D202-A)") (class "Default")
      (node (ref "D202") (pin "1") (pinfunction "A_1") (pintype "passive"))
      (node (ref "S202") (pin "1") (pinfunction "1_1") (pintype "passive"))
    )
    (net (code "22") (name "Net-(D203-A)") (class "Default")
      (node (ref "D203") (pin "1") (pinfunction "A_1") (pintype "passive"))
      (node (ref "S203") (pin "1") (pinfunction "1_1") (pintype "passive"))
    )
    (net (code "23") (name "Net-(D204-A)") (class "Default")
      (node (ref "D204") (pin "1") (pinfunction "A_1") (pintype "passive"))
      (node (ref "S204") (pin "1") (pinfunction "1_1") (pintype "passive"))
    )
    (net (code "24") (name "Net-(D205-A)") (class "Default")
      (node (ref "D205") (pin "1") (pinfunction "A_1") (pintype "passive"))
      (node (ref "S205") (pin "1") (pinfunction "1_1") (pintype "passive"))
    )
    (net (code "25") (name "Net-(D206-A)") (class "Default")
      (node (ref "D206") (pin "1") (pinfunction "A_1") (pintype "passive"))
      (node (ref "S206") (pin "1") (pinfunction "1_1") (pintype "passive"))
    )
    (net (code "26") (name "Net-(D207-A)") (class "Default")
      (node (ref "D207") (pin "1") (pinfunction "A_1") (pintype "passive"))
      (node (ref "S207") (pin "1") (pinfunction "1_1") (pintype "passive"))
    )
    (net (code "27") (name "Net-(D208-A)") (class "Default")
      (node (ref "D208") (pin "1") (pinfunction "A_1") (pintype "passive"))
      (node (ref "S208") (pin "1") (pinfunction "1_1") (pintype "passive"))
    )
    (net (code "28") (name "Net-(D209-A)") (class "Default")
      (node (ref "D209") (pin "1") (pinfunction "A_1") (pintype "passive"))
      (node (ref "S209") (pin "1") (pinfunction "1_1") (pintype "passive"))
    )
    (net (code "29") (name "Net-(D210-A)") (class "Default")
      (node (ref "D210") (pin "1") (pinfunction "A_1") (pintype "passive"))
      (node (ref "S210") (pin "1") (pinfunction "1_1") (pintype "passive"))
    )
    (net (code "30") (name "Net-(D211-A)") (class "Default")
      (node (ref "D211") (pin "1") (pinfunction "A_1") (pintype "passive"))
      (node (ref "S211") (pin "1") (pinfunction "1_1") (pintype "passive"))
    )
    (net (code "31") (name "Net-(D212-A)") (class "Default")
      (node (ref "D212") (pin "1") (pinfunction "A_1") (pintype "passive"))
      (node (ref "S212") (pin "1") (pinfunction "1_1") (pintype "passive"))
    )
    (net (code "32") (name "Net-(D213-A)") (class "Default")
      (node (ref "D213") (pin "1") (pinfunction "A_1") (pintype "passive"))
      (node (ref "S213") (pin "1") (pinfunction "1_1") (pintype "passive"))
    )
    (net (code "33") (name "Net-(D214-A)") (class "Default")
      (node (ref "D214") (pin "1") (pinfunction "A_1") (pintype "passive"))
      (node (ref "S214") (pin "1") (pinfunction "1_1") (pintype "passive"))
    )
    (net (code "34") (name "Net-(D215-A)") (class "Default")
      (node (ref "D215") (pin "1") (pinfunction "A_1") (pintype "passive"))
      (node (ref "S215") (pin "1") (pinfunction "1_1") (pintype "passive"))
    )
    (net (code "35") (name "Net-(D216-A)") (class "Default")
      (node (ref "D216") (pin "1") (pinfunction "A_1") (pintype "passive"))
      (node (ref "S216") (pin "1") (pinfunction "1_1") (pintype "passive"))
    )
    (net (code "36") (name "Net-(D217-A)") (class "Default")
      (node (ref "D217") (pin "1") (pinfunction "A_1") (pintype "passive"))
      (node (ref "S217") (pin "1") (pinfunction "1_1") (pintype "passive"))
    )
    (net (code "37") (name "Net-(D218-A)") (class "Default")
      (node (ref "D218") (pin "1") (pinfunction "A_1") (pintype "passive"))
      (node (ref "S218") (pin "1") (pinfunction "1_1") (pintype "passive"))
    )
    (net (code "38") (name "Net-(D219-A)") (class "Default")
      (node (ref "D219") (pin "1") (pinfunction "A_1") (pintype "passive"))
      (node (ref "S219") (pin "1") (pinfunction "1_1") (pintype "passive"))
    )
    (net (code "39") (name "Net-(D220-A)") (class "Default")
      (node (ref "D220") (pin "1") (pinfunction "A_1") (pintype "passive"))
      (node (ref "S220") (pin "1") (pinfunction "1_1") (pintype "passive"))
    )
    (net (code "40") (name "Net-(D221-A)") (class "Default")
      (node (ref "D221") (pin "1") (pinfunction "A_1") (pintype "passive"))
      (node (ref "S221") (pin "1") (pinfunction "1_1") (pintype "passive"))
    )
    (net (code "41") (name "Net-(D222-A)") (class "Default")
      (node (ref "D222") (pin "1") (pinfunction "A_1") (pintype "passive"))
      (node (ref "S222") (pin "1") (pinfunction "1_1") (pintype "passive"))
    )
    (net (code "42") (name "Net-(D223-A)") (class "Default")
      (node (ref "D223") (pin "1") (pinfunction "A_1") (pintype "passive"))
      (node (ref "S223") (pin "1") (pinfunction "1_1") (pintype "passive"))
    )
    (net (code "43") (name "Net-(D224-A)") (class "Default")
      (node (ref "D224") (pin "1") (pinfunction "A_1") (pintype "passive"))
      (node (ref "S224") (pin "1") (pinfunction "1_1") (pintype "passive"))
    )
    (net (code "44") (name "Net-(D225-A)") (class "Default")
      (node (ref "D225") (pin "1") (pinfunction "A_1") (pintype "passive"))
      (node (ref "S225") (pin "1") (pinfunction "1_1") (pintype "passive"))
    )
    (net (code "45") (name "Net-(D226-A)") (class "Default")
      (node (ref "D226") (pin "1") (pinfunction "A_1") (pintype "passive"))
      (node (ref "S226") (pin "1") (pinfunction "1_1") (pintype "passive"))
    )
    (net (code "46") (name "Net-(D227-A)") (class "Default")
      (node (ref "D227") (pin "1") (pinfunction "A_1") (pintype "passive"))
      (node (ref "S227") (pin "1") (pinfunction "1_1") (pintype "passive"))
    )
    (net (code "47") (name "Net-(D228-A)") (class "Default")
      (node (ref "D228") (pin "1") (pinfunction "A_1") (pintype "passive"))
      (node (ref "S228") (pin "1") (pinfunction "1_1") (pintype "passive"))
    )
    (net (code "48") (name "Net-(D229-A)") (class "Default")
      (node (ref "D229") (pin "1") (pinfunction "A_1") (pintype "passive"))
      (node (ref "S229") (pin "1") (pinfunction "1_1") (pintype "passive"))
    )
    (net (code "49") (name "Net-(D230-A)") (class "Default")
      (node (ref "D230") (pin "1") (pinfunction "A_1") (pintype "passive"))
      (node (ref "S230") (pin "1") (pinfunction "1_1") (pintype "passive"))
    )
    (net (code "50") (name "Net-(D231-A)") (class "Default")
      (node (ref "D231") (pin "1") (pinfunction "A_1") (pintype "passive"))
      (node (ref "S231") (pin "1") (pinfunction "1_1") (pintype "passive"))
    )
    (net (code "51") (name "Net-(D232-A)") (class "Default")
      (node (ref "D232") (pin "1") (pinfunction "A_1") (pintype "passive"))
      (node (ref "S232") (pin "1") (pinfunction "1_1") (pintype "passive"))
    )
    (net (code "52") (name "Net-(D233-A)") (class "Default")
      (node (ref "D233") (pin "1") (pinfunction "A_1") (pintype "passive"))
      (node (ref "S233") (pin "1") (pinfunction "1_1") (pintype "passive"))
    )
    (net (code "53") (name "Net-(D234-A)") (class "Default")
      (node (ref "D234") (pin "1") (pinfunction "A_1") (pintype "passive"))
      (node (ref "S234") (pin "1") (pinfunction "1_1") (pintype "passive"))
    )
    (net (code "54") (name "Net-(D235-A)") (class "Default")
      (node (ref "D235") (pin "1") (pinfunction "A_1") (pintype "passive"))
      (node (ref "S235") (pin "1") (pinfunction "1_1") (pintype "passive"))
    )
    (net (code "55") (name "Net-(D236-A)") (class "Default")
      (node (ref "D236") (pin "1") (pinfunction "A_1") (pintype "passive"))
      (node (ref "S236") (pin "1") (pinfunction "1_1") (pintype "passive"))
    )
    (net (code "56") (name "Net-(D237-A)") (class "Default")
      (node (ref "D237") (pin "1") (pinfunction "A_1") (pintype "passive"))
      (node (ref "S237") (pin "1") (pinfunction "1_1") (pintype "passive"))
    )
    (net (code "57") (name "Net-(D238-A)") (class "Default")
      (node (ref "D238") (pin "1") (pinfunction "A_1") (pintype "passive"))
      (node (ref "S238") (pin "1") (pinfunction "1_1") (pintype "passive"))
    )
    (net (code "58") (name "Net-(D239-A)") (class "Default")
      (node (ref "D239") (pin "1") (pinfunction "A_1") (pintype "passive"))
      (node (ref "S239") (pin "1") (pinfunction "1_1") (pintype "passive"))
    )
    (net (code "59") (name "Net-(D240-A)") (class "Default")
      (node (ref "D240") (pin "1") (pinfunction "A_1") (pintype "passive"))
      (node (ref "S240") (pin "1") (pinfunction "1_1") (pintype "passive"))
    )
    (net (code "60") (name "Net-(D241-A)") (class "Default")
      (node (ref "D241") (pin "1") (pinfunction "A_1") (pintype "passive"))
      (node (ref "S241") (pin "1") (pinfunction "1_1") (pintype "passive"))
    )
    (net (code "61") (name "Net-(D242-A)") (class "Default")
      (node (ref "D242") (pin "1") (pinfunction "A_1") (pintype "passive"))
      (node (ref "S242") (pin "1") (pinfunction "1_1") (pintype "passive"))
    )
    (net (code "62") (name "Net-(D243-A)") (class "Default")
      (node (ref "D243") (pin "1") (pinfunction "A_1") (pintype "passive"))
      (node (ref "S243") (pin "1") (pinfunction "1_1") (pintype "passive"))
    )
    (net (code "63") (name "Net-(D244-A)") (class "Default")
      (node (ref "D244") (pin "1") (pinfunction "A_1") (pintype "passive"))
      (node (ref "S244") (pin "1") (pinfunction "1_1") (pintype "passive"))
    )
    (net (code "64") (name "Net-(D245-A)") (class "Default")
      (node (ref "D245") (pin "1") (pinfunction "A_1") (pintype "passive"))
      (node (ref "S245") (pin "1") (pinfunction "1_1") (pintype "passive"))
    )
    (net (code "65") (name "Net-(D246-A)") (class "Default")
      (node (ref "D246") (pin "1") (pinfunction "A_1") (pintype "passive"))
      (node (ref "S246") (pin "1") (pinfunction "1_1") (pintype "passive"))
    )
    (net (code "66") (name "Net-(D247-A)") (class "Default")
      (node (ref "D247") (pin "1") (pinfunction "A_1") (pintype "passive"))
      (node (ref "S247") (pin "1") (pinfunction "1_1") (pintype "passive"))
    )
    (net (code "67") (name "Net-(D248-A)") (class "Default")
      (node (ref "D248") (pin "1") (pinfunction "A_1") (pintype "passive"))
      (node (ref "S248") (pin "1") (pinfunction "1_1") (pintype "passive"))
    )
    (net (code "68") (name "Net-(D249-A)") (class "Default")
      (node (ref "D249") (pin "1") (pinfunction "A_1") (pintype "passive"))
      (node (ref "S249") (pin "1") (pinfunction "1_1") (pintype "passive"))
    )
    (net (code "69") (name "Net-(D250-A)") (class "Default")
      (node (ref "D250") (pin "1") (pinfunction "A_1") (pintype "passive"))
      (node (ref "S250") (pin "1") (pinfunction "1_1") (pintype "passive"))
    )
    (net (code "70") (name "Net-(D251-A)") (class "Default")
      (node (ref "D251") (pin "1") (pinfunction "A_1") (pintype "passive"))
      (node (ref "S251") (pin "1") (pinfunction "1_1") (pintype "passive"))
    )
    (net (code "71") (name "Net-(D252-A)") (class "Default")
      (node (ref "D252") (pin "1") (pinfunction "A_1") (pintype "passive"))
      (node (ref "S252") (pin "1") (pinfunction "1_1") (pintype "passive"))
    )
    (net (code "72") (name "Net-(D253-A)") (class "Default")
      (node (ref "D253") (pin "1") (pinfunction "A_1") (pintype "passive"))
      (node (ref "S253") (pin "1") (pinfunction "1_1") (pintype "passive"))
    )
    (net (code "73") (name "Net-(D254-A)") (class "Default")
      (node (ref "D254") (pin "1") (pinfunction "A_1") (pintype "passive"))
      (node (ref "S254") (pin "1") (pinfunction "1_1") (pintype "passive"))
    )
    (net (code "74") (name "Net-(D255-A)") (class "Default")
      (node (ref "D255") (pin "1") (pinfunction "A_1") (pintype "passive"))
      (node (ref "S255") (pin "1") (pinfunction "1_1") (pintype "passive"))
    )
    (net (code "75") (name "Net-(D256-A)") (class "Default")
      (node (ref "D256") (pin "1") (pinfunction "A_1") (pintype "passive"))
      (node (ref "S256") (pin "1") (pinfunction "1_1") (pintype "passive"))
    )
    (net (code "76") (name "Net-(D257-A)") (class "Default")
      (node (ref "D257") (pin "1") (pinfunction "A_1") (pintype "passive"))
      (node (ref "S257") (pin "1") (pinfunction "1_1") (pintype "passive"))
    )
    (net (code "77") (name "Net-(D258-A)") (class "Default")
      (node (ref "D258") (pin "1") (pinfunction "A_1") (pintype "passive"))
      (node (ref "S258") (pin "1") (pinfunction "1_1") (pintype "passive"))
    )
    (net (code "78") (name "Net-(D259-A)") (class "Default")
      (node (ref "D259") (pin "1") (pinfunction "A_1") (pintype "passive"))
      (node (ref "S259") (pin "1") (pinfunction "1_1") (pintype "passive"))
    )
    (net (code "79") (name "Net-(D260-A)") (class "Default")
      (node (ref "D260") (pin "1") (pinfunction "A_1") (pintype "passive"))
      (node (ref "S260") (pin "1") (pinfunction "1_1") (pintype "passive"))
    )
    (net (code "80") (name "Net-(D261-A)") (class "Default")
      (node (ref "D261") (pin "1") (pinfunction "A_1") (pintype "passive"))
      (node (ref "S261") (pin "1") (pinfunction "1_1") (pintype "passive"))
    )
    (net (code "81") (name "Net-(D262-A)") (class "Default")
      (node (ref "D262") (pin "1") (pinfunction "A_1") (pintype "passive"))
      (node (ref "S262") (pin "1") (pinfunction "1_1") (pintype "passive"))
    )
    (net (code "82") (name "Net-(D263-A)") (class "Default")
      (node (ref "D263") (pin "1") (pinfunction "A_1") (pintype "passive"))
      (node (ref "S263") (pin "1") (pinfunction "1_1") (pintype "passive"))
    )
    (net (code "83") (name "Net-(D264-A)") (class "Default")
      (node (ref "D264") (pin "1") (pinfunction "A_1") (pintype "passive"))
      (node (ref "S264") (pin "1") (pinfunction "1_1") (pintype "passive"))
    )
    (net (code "84") (name "Net-(D265-A)") (class "Default")
      (node (ref "D265") (pin "1") (pinfunction "A_1") (pintype "passive"))
      (node (ref "S265") (pin "1") (pinfunction "1_1") (pintype "passive"))
    )
    (net (code "85") (name "Net-(D266-A)") (class "Default")
      (node (ref "D266") (pin "1") (pinfunction "A_1") (pintype "passive"))
      (node (ref "S266") (pin "1") (pinfunction "1_1") (pintype "passive"))
    )
    (net (code "86") (name "Net-(D267-A)") (class "Default")
      (node (ref "D267") (pin "1") (pinfunction "A_1") (pintype "passive"))
      (node (ref "S267") (pin "1") (pinfunction "1_1") (pintype "passive"))
    )
    (net (code "87") (name "Net-(D268-A)") (class "Default")
      (node (ref "D268") (pin "1") (pinfunction "A_1") (pintype "passive"))
      (node (ref "S268") (pin "1") (pinfunction "1_1") (pintype "passive"))
    )
    (net (code "88") (name "Net-(D269-A)") (class "Default")
      (node (ref "D269") (pin "1") (pinfunction "A_1") (pintype "passive"))
      (node (ref "S269") (pin "1") (pinfunction "1_1") (pintype "passive"))
    )
    (net (code "89") (name "Net-(D270-A)") (class "Default")
      (node (ref "D270") (pin "1") (pinfunction "A_1") (pintype "passive"))
      (node (ref "S270") (pin "1") (pinfunction "1_1") (pintype "passive"))
    )
  )
)
